# power_mux.net
KiCad netlist of a schematic drawn in Altium Designer
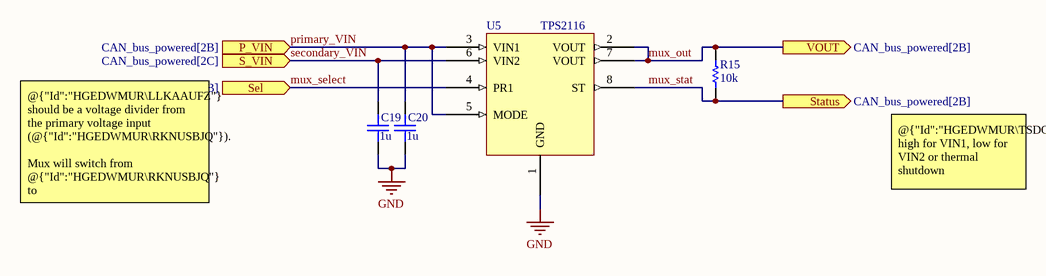
[diagram p0: power_mux.SchDoc]

(export (version "E")
  (design (tool "Eeschema 10.0.6"))
  (components
    (comp (ref "C19")
      (value "1u")
      (description "Capacitor")
      (libsource (lib "drfc_schlib") (part "Capacitor"))
    )
    (comp (ref "C20")
      (value "1u")
      (description "Capacitor")
      (libsource (lib "drfc_schlib") (part "Capacitor"))
    )
    (comp (ref "R15")
      (value "10k")
      (description "Resistor")
      (libsource (lib "drfc_schlib") (part "Resistor"))
    )
    (comp (ref "U5")
      (value "TPS2116")
      (description "1.6 V to 5.5 V, 2.5-A Low IQ Power Mux with Manual and Priority Switchover")
      (libsource (lib "drfc_schlib") (part "TPS2116"))
    )
  )
  (nets
    (net (code "1") (name "/mux_out") (class "Default")
      (node (ref "R15") (pin "2") (pinfunction "2_2") (pintype "passive"))
      (node (ref "U5") (pin "2") (pinfunction "VOUT_2") (pintype "output"))
      (node (ref "U5") (pin "7") (pinfunction "VOUT_7") (pintype "output"))
    )
    (net (code "2") (name "/mux_select") (class "Default")
      (node (ref "U5") (pin "4") (pinfunction "PR1_4") (pintype "input"))
    )
    (net (code "3") (name "/mux_stat") (class "Default")
      (node (ref "R15") (pin "1") (pinfunction "1_1") (pintype "passive"))
      (node (ref "U5") (pin "8") (pinfunction "ST_8") (pintype "output"))
    )
    (net (code "4") (name "/primary_VIN") (class "Default")
      (node (ref "C20") (pin "2") (pinfunction "2_2") (pintype "passive"))
      (node (ref "U5") (pin "3") (pinfunction "VIN1_3") (pintype "input"))
      (node (ref "U5") (pin "5") (pinfunction "MODE_5") (pintype "input"))
    )
    (net (code "5") (name "/secondary_VIN") (class "Default")
      (node (ref "C19") (pin "2") (pinfunction "2_2") (pintype "passive"))
      (node (ref "U5") (pin "6") (pinfunction "VIN2_6") (pintype "input"))
    )
    (net (code "6") (name "GND") (class "Default")
      (node (ref "C19") (pin "1") (pinfunction "1_1") (pintype "passive"))
      (node (ref "C20") (pin "1") (pinfunction "1_1") (pintype "passive"))
      (node (ref "U5") (pin "1") (pinfunction "GND_1") (pintype "power_in"))
    )
  )
)
